# Wiper_Control.net
KiCad netlist of a schematic drawn in EAGLE
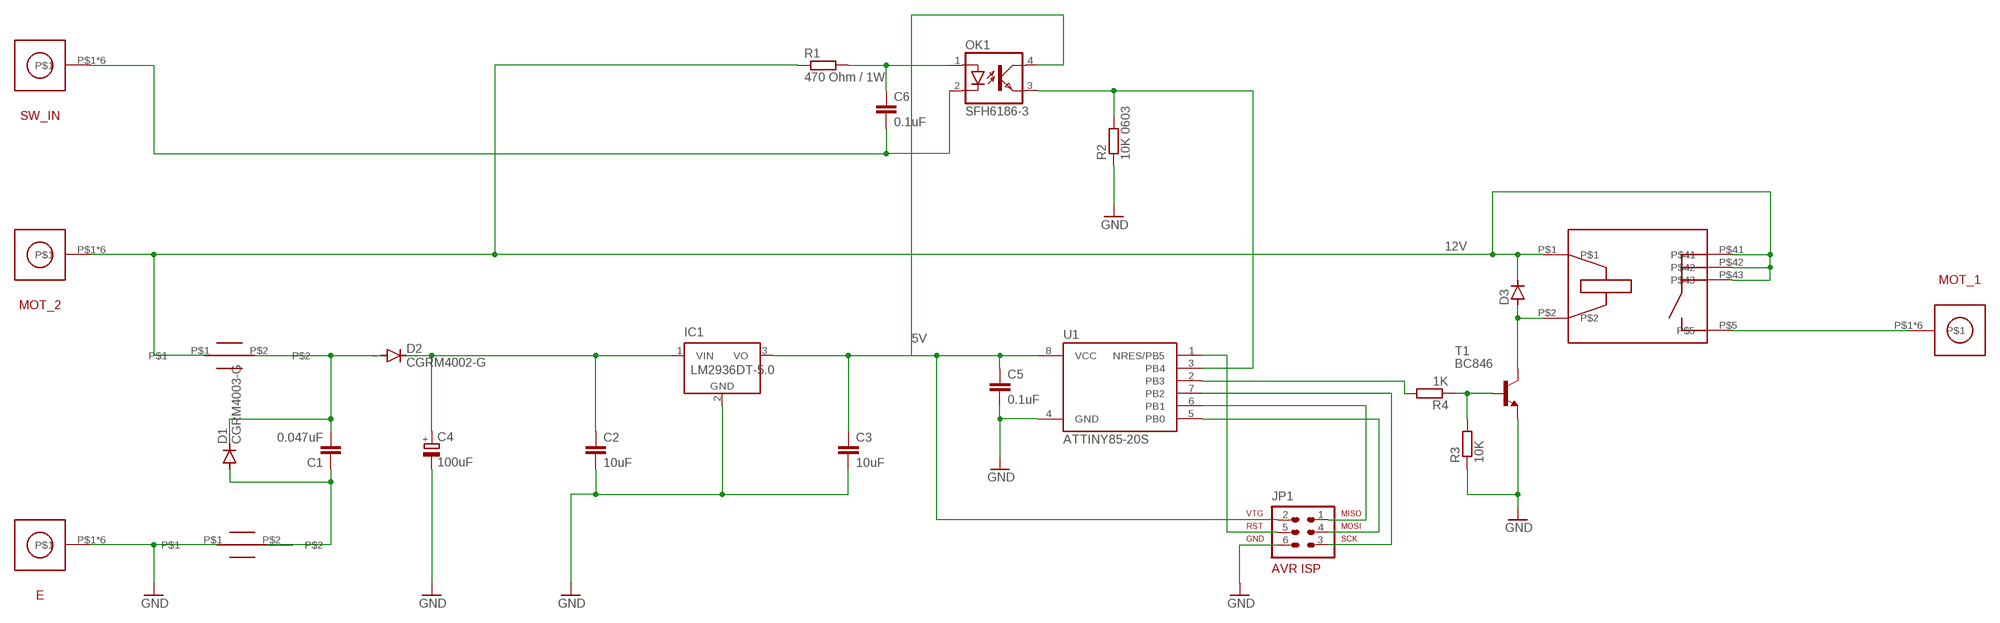
[diagram p0: schematic, sheet 1]

(export (version "E")
  (design (tool "Eeschema 10.0.6"))
  (components
    (comp (ref "C1")
      (value "0.047uF")
      (footprint "eagle-import:C0603")
      (libsource (lib "eagle-import") (part "C-EUC0603"))
    )
    (comp (ref "C2")
      (value "10uF")
      (footprint "eagle-import:C0805")
      (libsource (lib "eagle-import") (part "C-EUC0805"))
    )
    (comp (ref "C3")
      (value "10uF")
      (footprint "eagle-import:C0805")
      (libsource (lib "eagle-import") (part "C-EUC0805"))
    )
    (comp (ref "C4")
      (value "100uF")
      (footprint "eagle-import:E2,5-7")
      (libsource (lib "eagle-import") (part "CPOL-EUE2.5-7"))
    )
    (comp (ref "C5")
      (value "0.1uF")
      (footprint "eagle-import:C0603")
      (libsource (lib "eagle-import") (part "C-EUC0603"))
    )
    (comp (ref "C6")
      (value "0.1uF")
      (footprint "eagle-import:C0603")
      (libsource (lib "eagle-import") (part "C-EUC0603"))
    )
    (comp (ref "D1")
      (value "CGRM4003-G")
      (footprint "eagle-import:SOD-123_MINI-SMA")
      (libsource (lib "eagle-import") (part "CGRM400-G3"))
    )
    (comp (ref "D2")
      (value "CGRM4002-G")
      (footprint "eagle-import:SOD-123_MINI-SMA")
      (libsource (lib "eagle-import") (part "CGRM400-G2"))
    )
    (comp (ref "D3")
      (value "D-SOD123")
      (footprint "eagle-import:SOD123")
      (libsource (lib "eagle-import") (part "D-SOD123"))
    )
    (comp (ref "E")
      (value "M5_SCREW_TERMINAL")
      (footprint "eagle-import:M5_SCREW_TERMINAL")
      (libsource (lib "eagle-import") (part "M5_SCREW_TERMINAL"))
    )
    (comp (ref "IC1")
      (value "LM2936DT-5.0")
      (footprint "eagle-import:TO252")
      (fields (field (name "MF") "NATIONAL SEMICONDUCTOR") (field (name "MPN") "LM2936DT-5.0/NOPB"))
      (libsource (lib "eagle-import") (part "LM2936?DT-5.0"))
    )
    (comp (ref "JP1")
      (value "AVR-ISP-6")
      (footprint "eagle-import:AVR-ISP-6")
      (libsource (lib "eagle-import") (part "AVR-ISP-6"))
    )
    (comp (ref "MOT_1")
      (value "M5_SCREW_TERMINAL")
      (footprint "eagle-import:M5_SCREW_TERMINAL")
      (libsource (lib "eagle-import") (part "M5_SCREW_TERMINAL"))
    )
    (comp (ref "MOT_2")
      (value "M5_SCREW_TERMINAL")
      (footprint "eagle-import:M5_SCREW_TERMINAL")
      (libsource (lib "eagle-import") (part "M5_SCREW_TERMINAL"))
    )
    (comp (ref "OK1")
      (value "SFH6186-3")
      (footprint "eagle-import:SMD4-7")
      (fields (field (name "MF") "VISHAY/TELEFUNKEN"))
      (libsource (lib "eagle-import") (part "SFH618?6-3"))
    )
    (comp (ref "R1")
      (value "470 Ohm / 1W")
      (footprint "eagle-import:R2512")
      (libsource (lib "eagle-import") (part "R-EU_R2512"))
    )
    (comp (ref "R2")
      (value "10K 0603")
      (footprint "eagle-import:R0603")
      (libsource (lib "eagle-import") (part "R-EU_R0603"))
    )
    (comp (ref "R3")
      (value "10K")
      (footprint "eagle-import:R0603")
      (libsource (lib "eagle-import") (part "R-EU_R0603"))
    )
    (comp (ref "R4")
      (value "1K")
      (footprint "eagle-import:R0603")
      (libsource (lib "eagle-import") (part "R-EU_R0603"))
    )
    (comp (ref "SW_IN")
      (value "M5_SCREW_TERMINAL")
      (footprint "eagle-import:M5_SCREW_TERMINAL")
      (libsource (lib "eagle-import") (part "M5_SCREW_TERMINAL"))
    )
    (comp (ref "T1")
      (value "BC846")
      (footprint "eagle-import:SOT23")
      (libsource (lib "eagle-import") (part "BC846"))
    )
    (comp (ref "U$1")
      (value "FBMJ2125")
      (footprint "eagle-import:FBMJ")
      (libsource (lib "eagle-import") (part "FBMJ2125"))
    )
    (comp (ref "U$2")
      (value "FBMJ2125")
      (footprint "eagle-import:FBMJ")
      (libsource (lib "eagle-import") (part "FBMJ2125"))
    )
    (comp (ref "U$3")
      (value "RELAY")
      (footprint "eagle-import:RELAY")
      (libsource (lib "eagle-import") (part "RELAY"))
    )
    (comp (ref "U1")
      (value "ATTINY85-20S")
      (footprint "eagle-import:SOIC8_EIAJ_208MIL")
      (libsource (lib "eagle-import") (part "ATTINY85S-20"))
    )
  )
  (nets
    (net (code "1") (name "/5V") (class "Default")
      (node (ref "C3") (pin "1") (pinfunction "1_1") (pintype "passive"))
      (node (ref "C5") (pin "1") (pinfunction "1_1") (pintype "passive"))
      (node (ref "IC1") (pin "3") (pinfunction "VO_3") (pintype "passive"))
      (node (ref "JP1") (pin "2") (pinfunction "2_2") (pintype "passive"))
      (node (ref "OK1") (pin "4") (pinfunction "COL_4") (pintype "passive"))
      (node (ref "U1") (pin "8") (pinfunction "VCC_8") (pintype "power_in"))
    )
    (net (code "2") (name "/12V") (class "Default")
      (node (ref "D3") (pin "1") (pinfunction "C_1") (pintype "passive"))
      (node (ref "MOT_2") (pin "P$1") (pinfunction "P$1_P$1") (pintype "bidirectional"))
      (node (ref "MOT_2") (pin "P$2") (pinfunction "P$1_P$2") (pintype "bidirectional"))
      (node (ref "MOT_2") (pin "P$3") (pinfunction "P$1_P$3") (pintype "bidirectional"))
      (node (ref "MOT_2") (pin "P$4") (pinfunction "P$1_P$4") (pintype "bidirectional"))
      (node (ref "MOT_2") (pin "P$5") (pinfunction "P$1_P$5") (pintype "bidirectional"))
      (node (ref "MOT_2") (pin "P$6") (pinfunction "P$1_P$6") (pintype "bidirectional"))
      (node (ref "R1") (pin "1") (pinfunction "1_1") (pintype "passive"))
      (node (ref "U$1") (pin "P$1") (pinfunction "P$1_P$1") (pintype "bidirectional"))
      (node (ref "U$3") (pin "P$1") (pinfunction "P$1_P$1") (pintype "bidirectional"))
      (node (ref "U$3") (pin "P$41") (pinfunction "P$41_P$41") (pintype "bidirectional"))
      (node (ref "U$3") (pin "P$42") (pinfunction "P$42_P$42") (pintype "bidirectional"))
      (node (ref "U$3") (pin "P$43") (pinfunction "P$43_P$43") (pintype "bidirectional"))
    )
    (net (code "3") (name "GND") (class "Default")
      (node (ref "C2") (pin "2") (pinfunction "2_2") (pintype "passive"))
      (node (ref "C3") (pin "2") (pinfunction "2_2") (pintype "passive"))
      (node (ref "C4") (pin "-") (pinfunction "-_-") (pintype "passive"))
      (node (ref "C5") (pin "2") (pinfunction "2_2") (pintype "passive"))
      (node (ref "E") (pin "P$1") (pinfunction "P$1_P$1") (pintype "bidirectional"))
      (node (ref "E") (pin "P$2") (pinfunction "P$1_P$2") (pintype "bidirectional"))
      (node (ref "E") (pin "P$3") (pinfunction "P$1_P$3") (pintype "bidirectional"))
      (node (ref "E") (pin "P$4") (pinfunction "P$1_P$4") (pintype "bidirectional"))
      (node (ref "E") (pin "P$5") (pinfunction "P$1_P$5") (pintype "bidirectional"))
      (node (ref "E") (pin "P$6") (pinfunction "P$1_P$6") (pintype "bidirectional"))
      (node (ref "IC1") (pin "2") (pinfunction "GND_2") (pintype "passive"))
      (node (ref "JP1") (pin "6") (pinfunction "6_6") (pintype "passive"))
      (node (ref "R2") (pin "1") (pinfunction "1_1") (pintype "passive"))
      (node (ref "R3") (pin "1") (pinfunction "1_1") (pintype "passive"))
      (node (ref "T1") (pin "2") (pinfunction "E_2") (pintype "passive"))
      (node (ref "U$2") (pin "P$1") (pinfunction "P$1_P$1") (pintype "bidirectional"))
      (node (ref "U1") (pin "4") (pinfunction "GND_4") (pintype "power_in"))
    )
    (net (code "4") (name "Net-(C1-Pad1)") (class "Default")
      (node (ref "C1") (pin "1") (pinfunction "1_1") (pintype "passive"))
      (node (ref "D1") (pin "A") (pinfunction "A_A") (pintype "passive"))
      (node (ref "U$2") (pin "P$2") (pinfunction "P$2_P$2") (pintype "bidirectional"))
    )
    (net (code "5") (name "Net-(C1-Pad2)") (class "Default")
      (node (ref "C1") (pin "2") (pinfunction "2_2") (pintype "passive"))
      (node (ref "D1") (pin "C") (pinfunction "C_C") (pintype "passive"))
      (node (ref "D2") (pin "A") (pinfunction "A_A") (pintype "passive"))
      (node (ref "U$1") (pin "P$2") (pinfunction "P$2_P$2") (pintype "bidirectional"))
    )
    (net (code "6") (name "Net-(D3-A)") (class "Default")
      (node (ref "D3") (pin "2") (pinfunction "A_2") (pintype "passive"))
      (node (ref "T1") (pin "3") (pinfunction "C_3") (pintype "passive"))
      (node (ref "U$3") (pin "P$2") (pinfunction "P$2_P$2") (pintype "bidirectional"))
    )
    (net (code "7") (name "Net-(IC1-VIN)") (class "Default")
      (node (ref "C2") (pin "1") (pinfunction "1_1") (pintype "passive"))
      (node (ref "C4") (pin "+") (pinfunction "+_+") (pintype "passive"))
      (node (ref "D2") (pin "C") (pinfunction "C_C") (pintype "passive"))
      (node (ref "IC1") (pin "1") (pinfunction "VIN_1") (pintype "input"))
    )
    (net (code "8") (name "Net-(MOT_1-P$1-PadP$2)") (class "Default")
      (node (ref "MOT_1") (pin "P$1") (pinfunction "P$1_P$1") (pintype "bidirectional"))
      (node (ref "MOT_1") (pin "P$2") (pinfunction "P$1_P$2") (pintype "bidirectional"))
      (node (ref "MOT_1") (pin "P$3") (pinfunction "P$1_P$3") (pintype "bidirectional"))
      (node (ref "MOT_1") (pin "P$4") (pinfunction "P$1_P$4") (pintype "bidirectional"))
      (node (ref "MOT_1") (pin "P$5") (pinfunction "P$1_P$5") (pintype "bidirectional"))
      (node (ref "MOT_1") (pin "P$6") (pinfunction "P$1_P$6") (pintype "bidirectional"))
      (node (ref "U$3") (pin "P$5") (pinfunction "P$5_P$5") (pintype "bidirectional"))
    )
    (net (code "9") (name "Net-(OK1-A)") (class "Default")
      (node (ref "C6") (pin "1") (pinfunction "1_1") (pintype "passive"))
      (node (ref "OK1") (pin "1") (pinfunction "A_1") (pintype "passive"))
      (node (ref "R1") (pin "2") (pinfunction "2_2") (pintype "passive"))
    )
    (net (code "10") (name "Net-(OK1-C)") (class "Default")
      (node (ref "C6") (pin "2") (pinfunction "2_2") (pintype "passive"))
      (node (ref "OK1") (pin "2") (pinfunction "C_2") (pintype "passive"))
      (node (ref "SW_IN") (pin "P$1") (pinfunction "P$1_P$1") (pintype "bidirectional"))
      (node (ref "SW_IN") (pin "P$2") (pinfunction "P$1_P$2") (pintype "bidirectional"))
      (node (ref "SW_IN") (pin "P$3") (pinfunction "P$1_P$3") (pintype "bidirectional"))
      (node (ref "SW_IN") (pin "P$4") (pinfunction "P$1_P$4") (pintype "bidirectional"))
      (node (ref "SW_IN") (pin "P$5") (pinfunction "P$1_P$5") (pintype "bidirectional"))
      (node (ref "SW_IN") (pin "P$6") (pinfunction "P$1_P$6") (pintype "bidirectional"))
    )
    (net (code "11") (name "Net-(OK1-EMIT)") (class "Default")
      (node (ref "OK1") (pin "3") (pinfunction "EMIT_3") (pintype "passive"))
      (node (ref "R2") (pin "2") (pinfunction "2_2") (pintype "passive"))
      (node (ref "U1") (pin "3") (pinfunction "PB4_3") (pintype "bidirectional"))
    )
    (net (code "12") (name "Net-(T1-B)") (class "Default")
      (node (ref "R3") (pin "2") (pinfunction "2_2") (pintype "passive"))
      (node (ref "R4") (pin "1") (pinfunction "1_1") (pintype "passive"))
      (node (ref "T1") (pin "1") (pinfunction "B_1") (pintype "passive"))
    )
    (net (code "13") (name "Net-(U1-NRES{slash}PB5)") (class "Default")
      (node (ref "JP1") (pin "5") (pinfunction "5_5") (pintype "passive"))
      (node (ref "U1") (pin "1") (pinfunction "NRES/PB5_1") (pintype "bidirectional"))
    )
    (net (code "14") (name "Net-(U1-PB0)") (class "Default")
      (node (ref "JP1") (pin "4") (pinfunction "4_4") (pintype "passive"))
      (node (ref "U1") (pin "5") (pinfunction "PB0_5") (pintype "bidirectional"))
    )
    (net (code "15") (name "Net-(U1-PB1)") (class "Default")
      (node (ref "JP1") (pin "1") (pinfunction "1_1") (pintype "passive"))
      (node (ref "U1") (pin "6") (pinfunction "PB1_6") (pintype "bidirectional"))
    )
    (net (code "16") (name "Net-(U1-PB2)") (class "Default")
      (node (ref "JP1") (pin "3") (pinfunction "3_3") (pintype "passive"))
      (node (ref "U1") (pin "7") (pinfunction "PB2_7") (pintype "bidirectional"))
    )
    (net (code "17") (name "Net-(U1-PB3)") (class "Default")
      (node (ref "R4") (pin "2") (pinfunction "2_2") (pintype "passive"))
      (node (ref "U1") (pin "2") (pinfunction "PB3_2") (pintype "bidirectional"))
    )
  )
)
